# Sheet1.net
KiCad netlist of a schematic drawn in Altium Designer
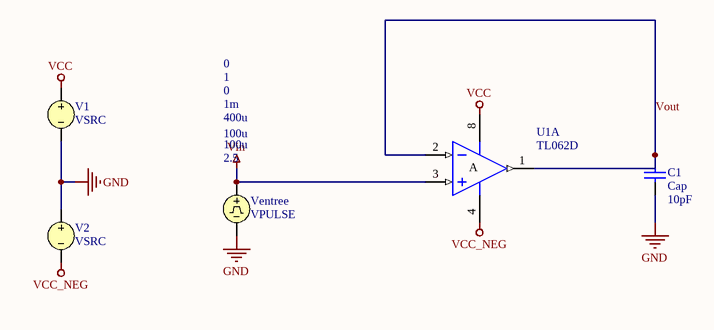
[diagram p0: Sheet1.SchDoc]

(export (version "E")
  (design (tool "Eeschema 10.0.6"))
  (components
    (comp (ref "C1")
      (value "Cap")
      (footprint "RAD-0.3")
      (description "Capacitor")
      (fields (field (name "ALTIUM_VALUE") "10pF") (field (name "PUBLISHER") "Altium Limited"))
      (libsource (lib "Miscellaneous Devices") (part "Cap"))
    )
    (comp (ref "U1")
      (value "TL062D")
      (footprint "D008_L")
      (description "Low-Power JFET-Input Operational Amplifier")
      (fields (field (name "PUBLISHER") "Altium Limited"))
      (libsource (lib "TI Operational Amplifier") (part "TL062D"))
    )
    (comp (ref "V1")
      (value "VSRC")
      (description "Voltage Source")
      (fields (field (name "PUBLISHER") "Altium Limited"))
      (libsource (lib "Simulation Sources") (part "VSRC"))
    )
    (comp (ref "V2")
      (value "VSRC")
      (description "Voltage Source")
      (fields (field (name "PUBLISHER") "Altium Limited"))
      (libsource (lib "Simulation Sources") (part "VSRC"))
    )
    (comp (ref "Ventree")
      (value "VPULSE")
      (description "Pulse Voltage Source")
      (fields
        (field (name "PULSED VALUE") "2.5")
        (field (name "RISE TIME") "100u")
        (field (name "FALL TIME") "100u")
        (field (name "PULSE WIDTH") "400u")
        (field (name "PERIOD") "1m")
        (field (name "DC MAGNITUDE") "0")
        (field (name "AC MAGNITUDE") "1")
        (field (name "AC PHASE") "0")
        (field (name "PUBLISHER") "Altium Limited")
      )
      (libsource (lib "Simulation Sources") (part "VPULSE"))
    )
  )
  (nets
    (net (code "1") (name "/Vout") (class "Default")
      (node (ref "C1") (pin "2") (pinfunction "2_2") (pintype "passive"))
      (node (ref "U1") (pin "1") (pinfunction "OUT_1") (pintype "output"))
      (node (ref "U1") (pin "2") (pinfunction "IN-_2") (pintype "input"))
    )
    (net (code "2") (name "GND") (class "Default")
      (node (ref "C1") (pin "1") (pinfunction "1_1") (pintype "passive"))
      (node (ref "V1") (pin "2") (pinfunction "2_2") (pintype "passive"))
      (node (ref "V2") (pin "1") (pinfunction "1_1") (pintype "passive"))
      (node (ref "Ventree") (pin "2") (pinfunction "2_2") (pintype "passive"))
    )
    (net (code "3") (name "VCC") (class "Default")
      (node (ref "U1") (pin "8") (pinfunction "V+_8") (pintype "power_in"))
      (node (ref "V1") (pin "1") (pinfunction "1_1") (pintype "passive"))
    )
    (net (code "4") (name "VCC_NEG") (class "Default")
      (node (ref "U1") (pin "4") (pinfunction "V-_4") (pintype "power_in"))
      (node (ref "V2") (pin "2") (pinfunction "2_2") (pintype "passive"))
    )
    (net (code "5") (name "Vin") (class "Default")
      (node (ref "U1") (pin "3") (pinfunction "IN+_3") (pintype "input"))
      (node (ref "Ventree") (pin "1") (pinfunction "1_1") (pintype "passive"))
    )
  )
)
